# ctrl_encoder.net
KiCad netlist of a schematic drawn in EAGLE
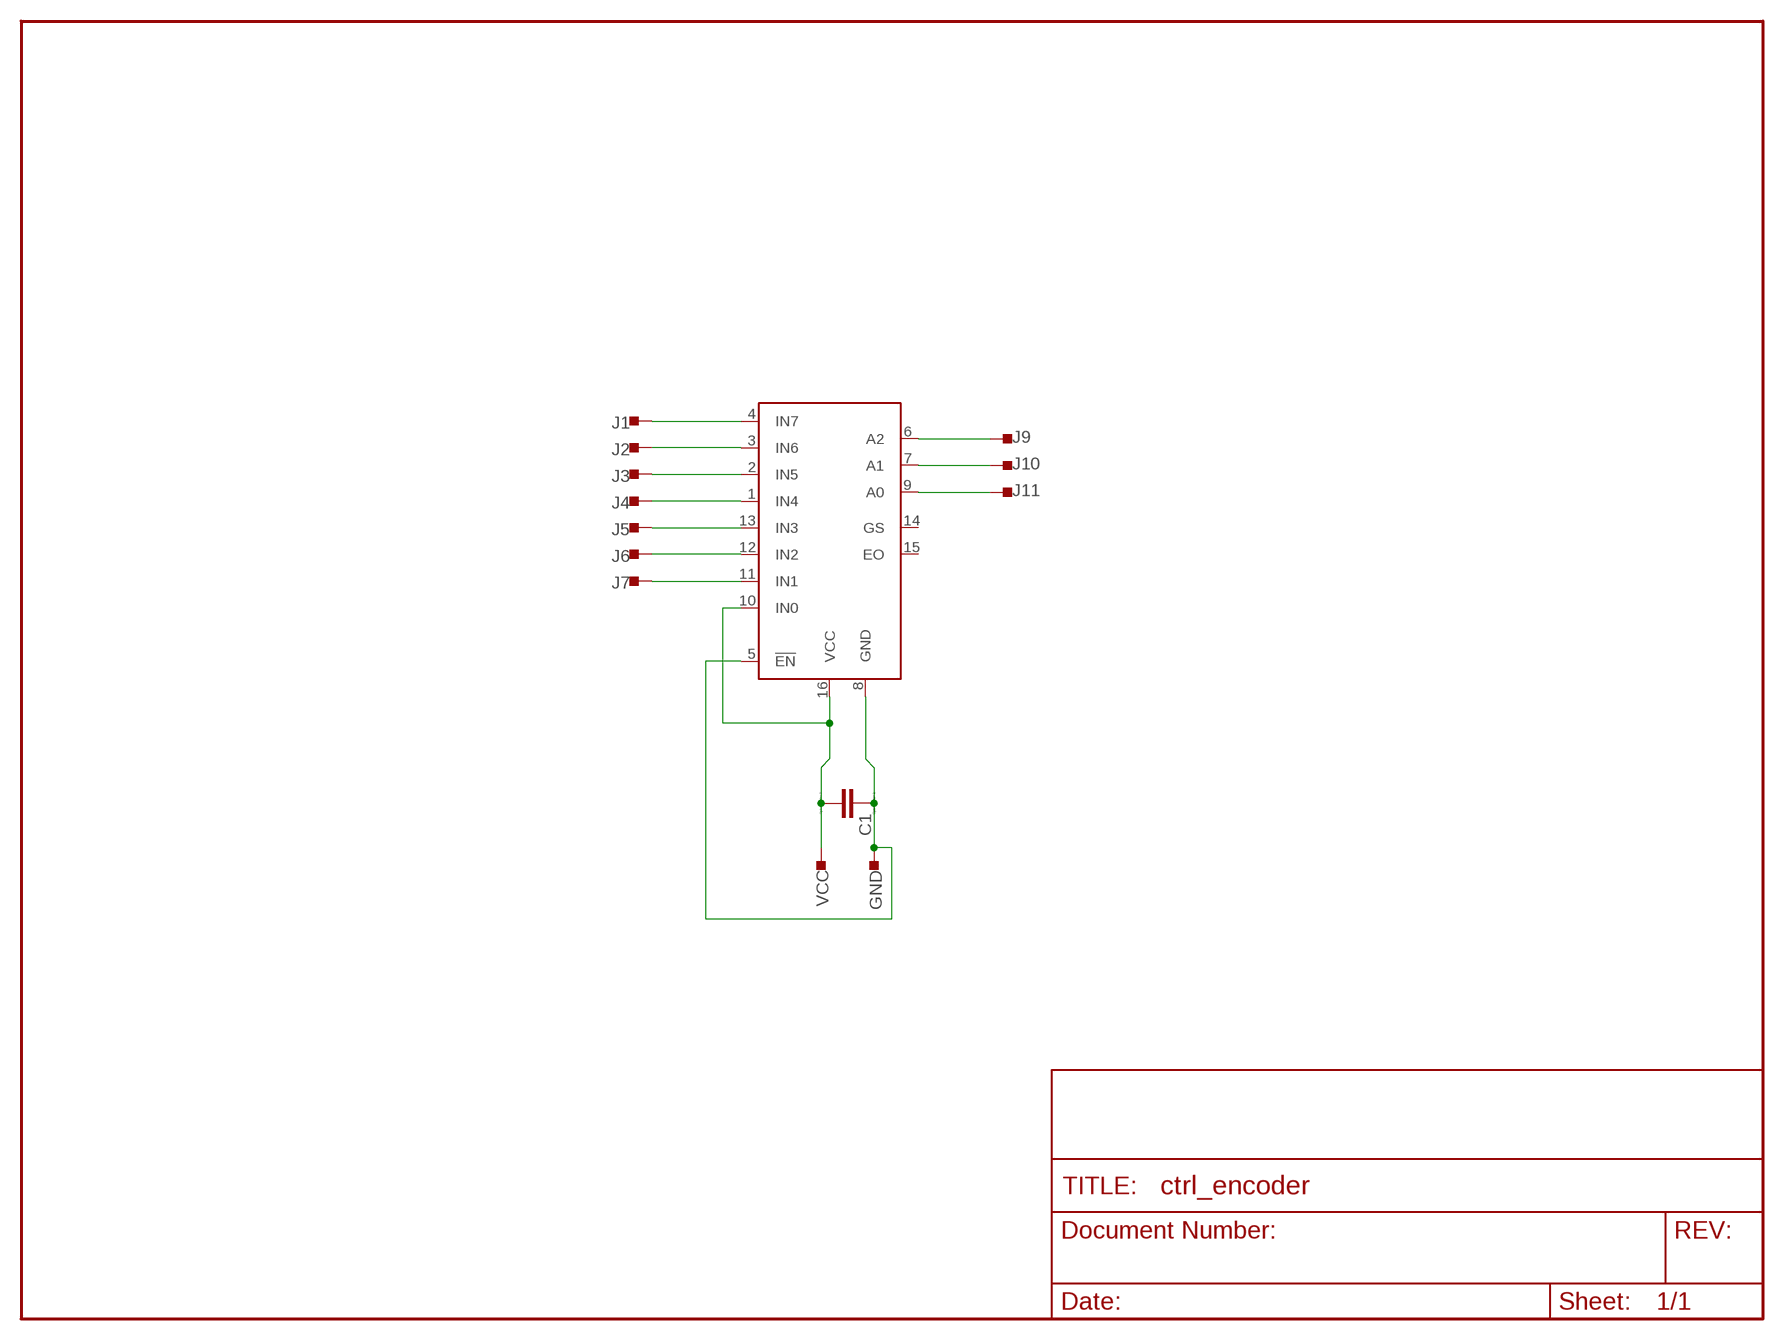
[diagram p0: schematic, sheet 1]

(export (version "E")
  (design (tool "Eeschema 10.0.6"))
  (components
    (comp (ref "C1") (value "C") (footprint "eagle-import:C0805") (libsource (lib "eagle-import") (part "C")))
    (comp (ref "GND")
      (value "PAD+SQUARE-1.5X1.5")
      (footprint "eagle-import:PAD-1.5X1.5")
      (libsource (lib "eagle-import") (part "PAD+SQUARE-1.5X1.5"))
    )
    (comp (ref "J1")
      (value "PAD+SQUARE-1.5X1.5")
      (footprint "eagle-import:PAD-1.5X1.5")
      (libsource (lib "eagle-import") (part "PAD+SQUARE-1.5X1.5"))
    )
    (comp (ref "J2")
      (value "PAD+SQUARE-1.5X1.5")
      (footprint "eagle-import:PAD-1.5X1.5")
      (libsource (lib "eagle-import") (part "PAD+SQUARE-1.5X1.5"))
    )
    (comp (ref "J3")
      (value "PAD+SQUARE-1.5X1.5")
      (footprint "eagle-import:PAD-1.5X1.5")
      (libsource (lib "eagle-import") (part "PAD+SQUARE-1.5X1.5"))
    )
    (comp (ref "J4")
      (value "PAD+SQUARE-1.5X1.5")
      (footprint "eagle-import:PAD-1.5X1.5")
      (libsource (lib "eagle-import") (part "PAD+SQUARE-1.5X1.5"))
    )
    (comp (ref "J5")
      (value "PAD+SQUARE-1.5X1.5")
      (footprint "eagle-import:PAD-1.5X1.5")
      (libsource (lib "eagle-import") (part "PAD+SQUARE-1.5X1.5"))
    )
    (comp (ref "J6")
      (value "PAD+SQUARE-1.5X1.5")
      (footprint "eagle-import:PAD-1.5X1.5")
      (libsource (lib "eagle-import") (part "PAD+SQUARE-1.5X1.5"))
    )
    (comp (ref "J7")
      (value "PAD+SQUARE-1.5X1.5")
      (footprint "eagle-import:PAD-1.5X1.5")
      (libsource (lib "eagle-import") (part "PAD+SQUARE-1.5X1.5"))
    )
    (comp (ref "J9")
      (value "PAD+SQUARE-1.5X1.5")
      (footprint "eagle-import:PAD-1.5X1.5")
      (libsource (lib "eagle-import") (part "PAD+SQUARE-1.5X1.5"))
    )
    (comp (ref "J10")
      (value "PAD+SQUARE-1.5X1.5")
      (footprint "eagle-import:PAD-1.5X1.5")
      (libsource (lib "eagle-import") (part "PAD+SQUARE-1.5X1.5"))
    )
    (comp (ref "J11")
      (value "PAD+SQUARE-1.5X1.5")
      (footprint "eagle-import:PAD-1.5X1.5")
      (libsource (lib "eagle-import") (part "PAD+SQUARE-1.5X1.5"))
    )
    (comp (ref "U$1")
      (value "SN74HC148DR")
      (footprint "eagle-import:SO16")
      (libsource (lib "eagle-import") (part "SN74HC148DR"))
    )
    (comp (ref "VCC")
      (value "PAD+SQUARE-1.5X1.5")
      (footprint "eagle-import:PAD-1.5X1.5")
      (libsource (lib "eagle-import") (part "PAD+SQUARE-1.5X1.5"))
    )
  )
  (nets
    (net (code "1") (name "Net-(U$1-A0)") (class "Default")
      (node (ref "J11") (pin "PAD") (pinfunction "PAD_PAD") (pintype "passive"))
      (node (ref "U$1") (pin "9") (pinfunction "A0_9") (pintype "output"))
    )
    (net (code "2") (name "Net-(U$1-A1)") (class "Default")
      (node (ref "J10") (pin "PAD") (pinfunction "PAD_PAD") (pintype "passive"))
      (node (ref "U$1") (pin "7") (pinfunction "A1_7") (pintype "output"))
    )
    (net (code "3") (name "Net-(U$1-A2)") (class "Default")
      (node (ref "J9") (pin "PAD") (pinfunction "PAD_PAD") (pintype "passive"))
      (node (ref "U$1") (pin "6") (pinfunction "A2_6") (pintype "output"))
    )
    (net (code "4") (name "Net-(U$1-GND)") (class "Default")
      (node (ref "C1") (pin "1") (pinfunction "1_1") (pintype "passive"))
      (node (ref "GND") (pin "PAD") (pinfunction "PAD_PAD") (pintype "passive"))
      (node (ref "U$1") (pin "5") (pinfunction "~{EN}_5") (pintype "bidirectional"))
      (node (ref "U$1") (pin "8") (pinfunction "GND_8") (pintype "power_in"))
    )
    (net (code "5") (name "Net-(U$1-IN0)") (class "Default")
      (node (ref "C1") (pin "2") (pinfunction "2_2") (pintype "passive"))
      (node (ref "U$1") (pin "10") (pinfunction "IN0_10") (pintype "input"))
      (node (ref "U$1") (pin "16") (pinfunction "VCC_16") (pintype "power_in"))
      (node (ref "VCC") (pin "PAD") (pinfunction "PAD_PAD") (pintype "passive"))
    )
    (net (code "6") (name "Net-(U$1-IN1)") (class "Default")
      (node (ref "J7") (pin "PAD") (pinfunction "PAD_PAD") (pintype "passive"))
      (node (ref "U$1") (pin "11") (pinfunction "IN1_11") (pintype "input"))
    )
    (net (code "7") (name "Net-(U$1-IN2)") (class "Default")
      (node (ref "J6") (pin "PAD") (pinfunction "PAD_PAD") (pintype "passive"))
      (node (ref "U$1") (pin "12") (pinfunction "IN2_12") (pintype "input"))
    )
    (net (code "8") (name "Net-(U$1-IN3)") (class "Default")
      (node (ref "J5") (pin "PAD") (pinfunction "PAD_PAD") (pintype "passive"))
      (node (ref "U$1") (pin "13") (pinfunction "IN3_13") (pintype "input"))
    )
    (net (code "9") (name "Net-(U$1-IN4)") (class "Default")
      (node (ref "J4") (pin "PAD") (pinfunction "PAD_PAD") (pintype "passive"))
      (node (ref "U$1") (pin "1") (pinfunction "IN4_1") (pintype "input"))
    )
    (net (code "10") (name "Net-(U$1-IN5)") (class "Default")
      (node (ref "J3") (pin "PAD") (pinfunction "PAD_PAD") (pintype "passive"))
      (node (ref "U$1") (pin "2") (pinfunction "IN5_2") (pintype "input"))
    )
    (net (code "11") (name "Net-(U$1-IN6)") (class "Default")
      (node (ref "J2") (pin "PAD") (pinfunction "PAD_PAD") (pintype "passive"))
      (node (ref "U$1") (pin "3") (pinfunction "IN6_3") (pintype "input"))
    )
    (net (code "12") (name "Net-(U$1-IN7)") (class "Default")
      (node (ref "J1") (pin "PAD") (pinfunction "PAD_PAD") (pintype "passive"))
      (node (ref "U$1") (pin "4") (pinfunction "IN7_4") (pintype "input"))
    )
    (net (code "13") (name "unconnected-(U$1-EO-Pad15)") (class "Default")
      (node (ref "U$1") (pin "15") (pinfunction "EO_15") (pintype "output"))
    )
    (net (code "14") (name "unconnected-(U$1-GS-Pad14)") (class "Default")
      (node (ref "U$1") (pin "14") (pinfunction "GS_14") (pintype "output"))
    )
  )
)
